# Blue_Pill_-_Display.net
KiCad netlist of a schematic drawn in Altium Designer
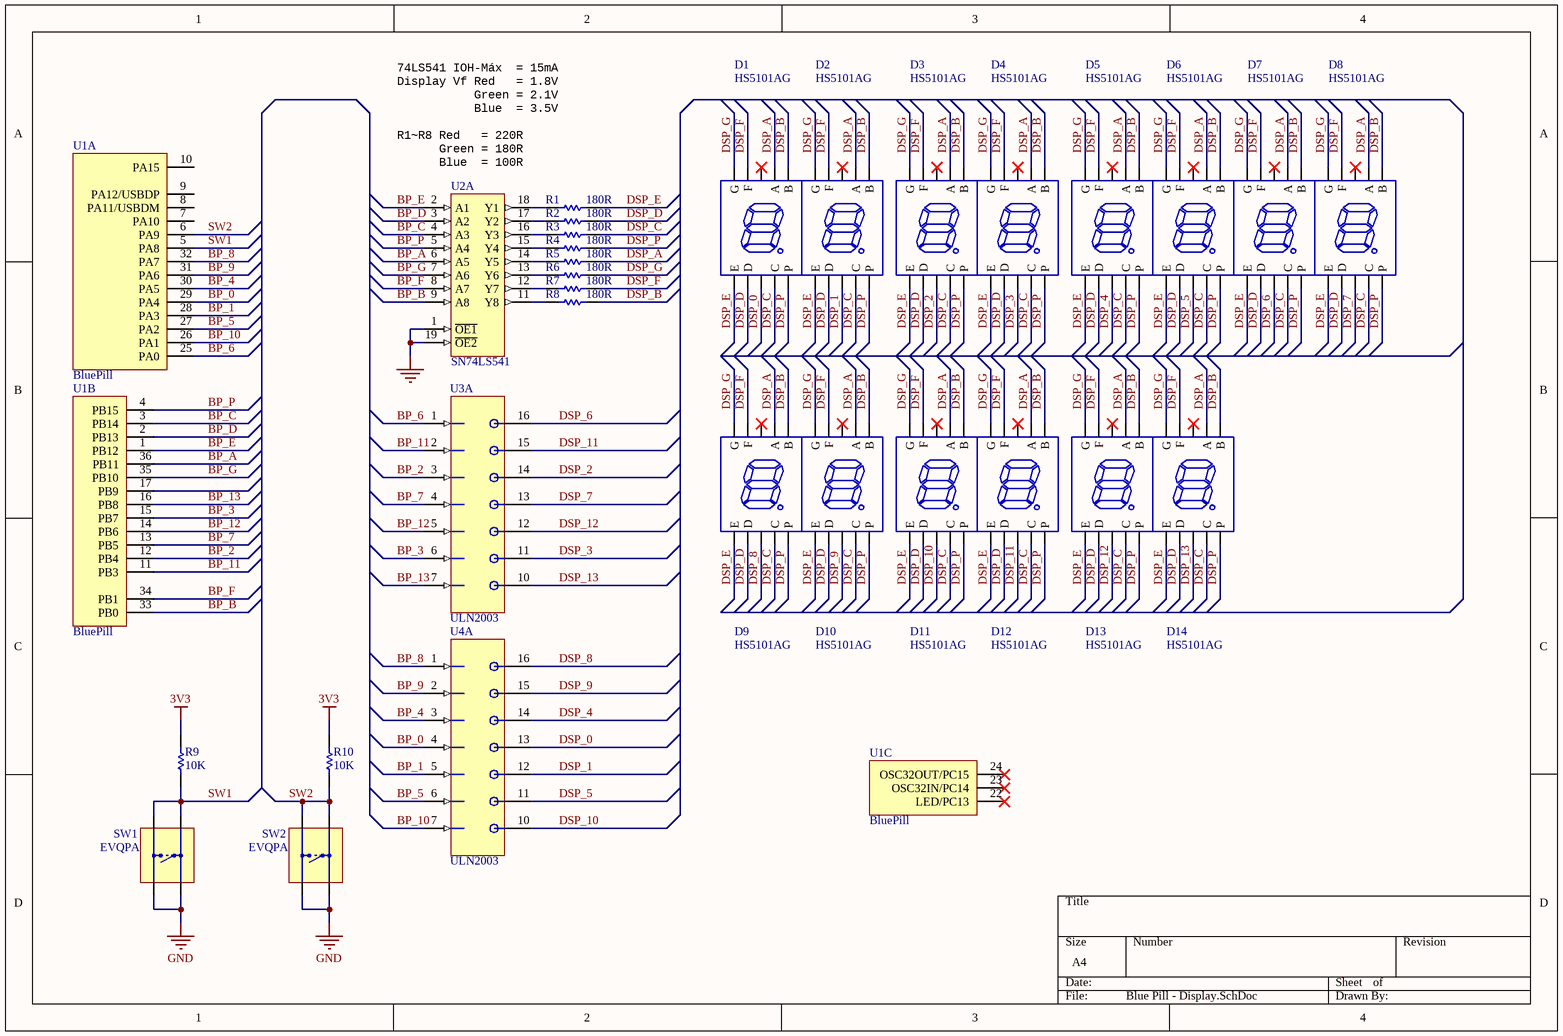
[diagram p0: Blue Pill - Display.SchDoc]

(export (version "E")
  (design (tool "Eeschema 10.0.6"))
  (components
    (comp (ref "D1")
      (value "HS5101AG")
      (footprint "HS5101AG")
      (description "Display 7-Segments Cathodo Common")
      (libsource (lib "Basic") (part "HS5101AG"))
    )
    (comp (ref "D2")
      (value "HS5101AG")
      (footprint "HS5101AG")
      (description "Display 7-Segments Cathodo Common")
      (libsource (lib "Basic") (part "HS5101AG"))
    )
    (comp (ref "D3")
      (value "HS5101AG")
      (footprint "HS5101AG")
      (description "Display 7-Segments Cathodo Common")
      (libsource (lib "Basic") (part "HS5101AG"))
    )
    (comp (ref "D4")
      (value "HS5101AG")
      (footprint "HS5101AG")
      (description "Display 7-Segments Cathodo Common")
      (libsource (lib "Basic") (part "HS5101AG"))
    )
    (comp (ref "D5")
      (value "HS5101AG")
      (footprint "HS5101AG")
      (description "Display 7-Segments Cathodo Common")
      (libsource (lib "Basic") (part "HS5101AG"))
    )
    (comp (ref "D6")
      (value "HS5101AG")
      (footprint "HS5101AG")
      (description "Display 7-Segments Cathodo Common")
      (libsource (lib "Basic") (part "HS5101AG"))
    )
    (comp (ref "D7")
      (value "HS5101AG")
      (footprint "HS5101AG")
      (description "Display 7-Segments Cathodo Common")
      (libsource (lib "Basic") (part "HS5101AG"))
    )
    (comp (ref "D8")
      (value "HS5101AG")
      (footprint "HS5101AG")
      (description "Display 7-Segments Cathodo Common")
      (libsource (lib "Basic") (part "HS5101AG"))
    )
    (comp (ref "D9")
      (value "HS5101AG")
      (footprint "HS5101AG")
      (description "Display 7-Segments Cathodo Common")
      (libsource (lib "Basic") (part "HS5101AG"))
    )
    (comp (ref "D10")
      (value "HS5101AG")
      (footprint "HS5101AG")
      (description "Display 7-Segments Cathodo Common")
      (libsource (lib "Basic") (part "HS5101AG"))
    )
    (comp (ref "D11")
      (value "HS5101AG")
      (footprint "HS5101AG")
      (description "Display 7-Segments Cathodo Common")
      (libsource (lib "Basic") (part "HS5101AG"))
    )
    (comp (ref "D12")
      (value "HS5101AG")
      (footprint "HS5101AG")
      (description "Display 7-Segments Cathodo Common")
      (libsource (lib "Basic") (part "HS5101AG"))
    )
    (comp (ref "D13")
      (value "HS5101AG")
      (footprint "HS5101AG")
      (description "Display 7-Segments Cathodo Common")
      (libsource (lib "Basic") (part "HS5101AG"))
    )
    (comp (ref "D14")
      (value "HS5101AG")
      (footprint "HS5101AG")
      (description "Display 7-Segments Cathodo Common")
      (libsource (lib "Basic") (part "HS5101AG"))
    )
    (comp (ref "R1")
      (value "180R")
      (footprint "0805")
      (description "Resistor")
      (libsource (lib "Basic") (part "Resistor"))
    )
    (comp (ref "R2")
      (value "180R")
      (footprint "0805")
      (description "Resistor")
      (libsource (lib "Basic") (part "Resistor"))
    )
    (comp (ref "R3")
      (value "180R")
      (footprint "0805")
      (description "Resistor")
      (libsource (lib "Basic") (part "Resistor"))
    )
    (comp (ref "R4")
      (value "180R")
      (footprint "0805")
      (description "Resistor")
      (libsource (lib "Basic") (part "Resistor"))
    )
    (comp (ref "R5")
      (value "180R")
      (footprint "0805")
      (description "Resistor")
      (libsource (lib "Basic") (part "Resistor"))
    )
    (comp (ref "R6")
      (value "180R")
      (footprint "0805")
      (description "Resistor")
      (libsource (lib "Basic") (part "Resistor"))
    )
    (comp (ref "R7")
      (value "180R")
      (footprint "0805")
      (description "Resistor")
      (libsource (lib "Basic") (part "Resistor"))
    )
    (comp (ref "R8")
      (value "180R")
      (footprint "0805")
      (description "Resistor")
      (libsource (lib "Basic") (part "Resistor"))
    )
    (comp (ref "R9")
      (value "10K")
      (footprint "0805")
      (description "Resistor")
      (libsource (lib "Basic") (part "Resistor"))
    )
    (comp (ref "R10")
      (value "10K")
      (footprint "0805")
      (description "Resistor")
      (libsource (lib "Basic") (part "Resistor"))
    )
    (comp (ref "SW1")
      (value "EVQPA")
      (footprint "EVQPAx09K")
      (description "5N Type Light Touch Switches")
      (libsource (lib "Panasonic") (part "EVQPA"))
    )
    (comp (ref "SW2")
      (value "EVQPA")
      (footprint "EVQPAx09K")
      (description "5N Type Light Touch Switches")
      (libsource (lib "Panasonic") (part "EVQPA"))
    )
    (comp (ref "U1")
      (value "BluePill")
      (footprint "Blue Pill")
      (description "STM32 Blue Pill")
      (libsource (lib "STM32 Blue Pill") (part "Blue Pill - Model 1"))
    )
    (comp (ref "U2")
      (value "SN74LS541")
      (footprint "PDIP20")
      (description "Octal Buffers and Line Drivers With 3-State Outputs")
      (libsource (lib "Texas Instruments") (part "SN74HC541 Type-2"))
    )
    (comp (ref "U3")
      (value "ULN2003")
      (footprint "PDIP16")
      (description "Seven Darlington arrays")
      (libsource (lib "ST Microelectronics") (part "UN200x - Model 1"))
    )
    (comp (ref "U4")
      (value "ULN2003")
      (footprint "PDIP16")
      (description "Seven Darlington arrays")
      (libsource (lib "ST Microelectronics") (part "UN200x - Model 1"))
    )
  )
  (nets
    (net (code "1") (name "/BP_0") (class "Default")
      (node (ref "U1") (pin "29") (pinfunction "PA4_29") (pintype "passive"))
      (node (ref "U4") (pin "4") (pinfunction "4_4") (pintype "input"))
    )
    (net (code "2") (name "/BP_1") (class "Default")
      (node (ref "U1") (pin "28") (pinfunction "PA3_28") (pintype "passive"))
      (node (ref "U4") (pin "5") (pinfunction "5_5") (pintype "input"))
    )
    (net (code "3") (name "/BP_2") (class "Default")
      (node (ref "U1") (pin "12") (pinfunction "PB4_12") (pintype "passive"))
      (node (ref "U3") (pin "3") (pinfunction "3_3") (pintype "input"))
    )
    (net (code "4") (name "/BP_3") (class "Default")
      (node (ref "U1") (pin "15") (pinfunction "PB7_15") (pintype "passive"))
      (node (ref "U3") (pin "6") (pinfunction "6_6") (pintype "input"))
    )
    (net (code "5") (name "/BP_4") (class "Default")
      (node (ref "U1") (pin "30") (pinfunction "PA5_30") (pintype "passive"))
      (node (ref "U4") (pin "3") (pinfunction "3_3") (pintype "input"))
    )
    (net (code "6") (name "/BP_5") (class "Default")
      (node (ref "U1") (pin "27") (pinfunction "PA2_27") (pintype "passive"))
      (node (ref "U4") (pin "6") (pinfunction "6_6") (pintype "input"))
    )
    (net (code "7") (name "/BP_6") (class "Default")
      (node (ref "U1") (pin "25") (pinfunction "PA0_25") (pintype "passive"))
      (node (ref "U3") (pin "1") (pinfunction "1_1") (pintype "input"))
    )
    (net (code "8") (name "/BP_7") (class "Default")
      (node (ref "U1") (pin "13") (pinfunction "PB5_13") (pintype "passive"))
      (node (ref "U3") (pin "4") (pinfunction "4_4") (pintype "input"))
    )
    (net (code "9") (name "/BP_8") (class "Default")
      (node (ref "U1") (pin "32") (pinfunction "PA7_32") (pintype "passive"))
      (node (ref "U4") (pin "1") (pinfunction "1_1") (pintype "input"))
    )
    (net (code "10") (name "/BP_9") (class "Default")
      (node (ref "U1") (pin "31") (pinfunction "PA6_31") (pintype "passive"))
      (node (ref "U4") (pin "2") (pinfunction "2_2") (pintype "input"))
    )
    (net (code "11") (name "/BP_10") (class "Default")
      (node (ref "U1") (pin "26") (pinfunction "PA1_26") (pintype "passive"))
      (node (ref "U4") (pin "7") (pinfunction "7_7") (pintype "input"))
    )
    (net (code "12") (name "/BP_11") (class "Default")
      (node (ref "U1") (pin "11") (pinfunction "PB3_11") (pintype "passive"))
      (node (ref "U3") (pin "2") (pinfunction "2_2") (pintype "input"))
    )
    (net (code "13") (name "/BP_12") (class "Default")
      (node (ref "U1") (pin "14") (pinfunction "PB6_14") (pintype "passive"))
      (node (ref "U3") (pin "5") (pinfunction "5_5") (pintype "input"))
    )
    (net (code "14") (name "/BP_13") (class "Default")
      (node (ref "U1") (pin "16") (pinfunction "PB8_16") (pintype "passive"))
      (node (ref "U3") (pin "7") (pinfunction "7_7") (pintype "input"))
    )
    (net (code "15") (name "/BP_A") (class "Default")
      (node (ref "U1") (pin "36") (pinfunction "PB11_36") (pintype "passive"))
      (node (ref "U2") (pin "6") (pinfunction "A5_6") (pintype "input"))
    )
    (net (code "16") (name "/BP_B") (class "Default")
      (node (ref "U1") (pin "33") (pinfunction "PB0_33") (pintype "passive"))
      (node (ref "U2") (pin "9") (pinfunction "A8_9") (pintype "input"))
    )
    (net (code "17") (name "/BP_C") (class "Default")
      (node (ref "U1") (pin "3") (pinfunction "PB14_3") (pintype "passive"))
      (node (ref "U2") (pin "4") (pinfunction "A3_4") (pintype "input"))
    )
    (net (code "18") (name "/BP_D") (class "Default")
      (node (ref "U1") (pin "2") (pinfunction "PB13_2") (pintype "passive"))
      (node (ref "U2") (pin "3") (pinfunction "A2_3") (pintype "input"))
    )
    (net (code "19") (name "/BP_E") (class "Default")
      (node (ref "U1") (pin "1") (pinfunction "PB12_1") (pintype "passive"))
      (node (ref "U2") (pin "2") (pinfunction "A1_2") (pintype "input"))
    )
    (net (code "20") (name "/BP_F") (class "Default")
      (node (ref "U1") (pin "34") (pinfunction "PB1_34") (pintype "passive"))
      (node (ref "U2") (pin "8") (pinfunction "A7_8") (pintype "input"))
    )
    (net (code "21") (name "/BP_G") (class "Default")
      (node (ref "U1") (pin "35") (pinfunction "PB10_35") (pintype "passive"))
      (node (ref "U2") (pin "7") (pinfunction "A6_7") (pintype "input"))
    )
    (net (code "22") (name "/BP_P") (class "Default")
      (node (ref "U1") (pin "4") (pinfunction "PB15_4") (pintype "passive"))
      (node (ref "U2") (pin "5") (pinfunction "A4_5") (pintype "input"))
    )
    (net (code "23") (name "/DSP_0") (class "Default")
      (node (ref "D1") (pin "3") (pinfunction "GND2_3") (pintype "power_in"))
      (node (ref "U4") (pin "13") (pinfunction "13_13") (pintype "open_collector"))
    )
    (net (code "24") (name "/DSP_1") (class "Default")
      (node (ref "D2") (pin "3") (pinfunction "GND2_3") (pintype "power_in"))
      (node (ref "U4") (pin "12") (pinfunction "12_12") (pintype "open_collector"))
    )
    (net (code "25") (name "/DSP_2") (class "Default")
      (node (ref "D3") (pin "3") (pinfunction "GND2_3") (pintype "power_in"))
      (node (ref "U3") (pin "14") (pinfunction "14_14") (pintype "open_collector"))
    )
    (net (code "26") (name "/DSP_3") (class "Default")
      (node (ref "D4") (pin "3") (pinfunction "GND2_3") (pintype "power_in"))
      (node (ref "U3") (pin "11") (pinfunction "11_11") (pintype "open_collector"))
    )
    (net (code "27") (name "/DSP_4") (class "Default")
      (node (ref "D5") (pin "3") (pinfunction "GND2_3") (pintype "power_in"))
      (node (ref "U4") (pin "14") (pinfunction "14_14") (pintype "open_collector"))
    )
    (net (code "28") (name "/DSP_5") (class "Default")
      (node (ref "D6") (pin "3") (pinfunction "GND2_3") (pintype "power_in"))
      (node (ref "U4") (pin "11") (pinfunction "11_11") (pintype "open_collector"))
    )
    (net (code "29") (name "/DSP_6") (class "Default")
      (node (ref "D7") (pin "3") (pinfunction "GND2_3") (pintype "power_in"))
      (node (ref "U3") (pin "16") (pinfunction "16_16") (pintype "open_collector"))
    )
    (net (code "30") (name "/DSP_7") (class "Default")
      (node (ref "D8") (pin "3") (pinfunction "GND2_3") (pintype "power_in"))
      (node (ref "U3") (pin "13") (pinfunction "13_13") (pintype "open_collector"))
    )
    (net (code "31") (name "/DSP_8") (class "Default")
      (node (ref "D9") (pin "3") (pinfunction "GND2_3") (pintype "power_in"))
      (node (ref "U4") (pin "16") (pinfunction "16_16") (pintype "open_collector"))
    )
    (net (code "32") (name "/DSP_9") (class "Default")
      (node (ref "D10") (pin "3") (pinfunction "GND2_3") (pintype "power_in"))
      (node (ref "U4") (pin "15") (pinfunction "15_15") (pintype "open_collector"))
    )
    (net (code "33") (name "/DSP_10") (class "Default")
      (node (ref "D11") (pin "3") (pinfunction "GND2_3") (pintype "power_in"))
      (node (ref "U4") (pin "10") (pinfunction "10_10") (pintype "open_collector"))
    )
    (net (code "34") (name "/DSP_11") (class "Default")
      (node (ref "D12") (pin "3") (pinfunction "GND2_3") (pintype "power_in"))
      (node (ref "U3") (pin "15") (pinfunction "15_15") (pintype "open_collector"))
    )
    (net (code "35") (name "/DSP_12") (class "Default")
      (node (ref "D13") (pin "3") (pinfunction "GND2_3") (pintype "power_in"))
      (node (ref "U3") (pin "12") (pinfunction "12_12") (pintype "open_collector"))
    )
    (net (code "36") (name "/DSP_13") (class "Default")
      (node (ref "D14") (pin "3") (pinfunction "GND2_3") (pintype "power_in"))
      (node (ref "U3") (pin "10") (pinfunction "10_10") (pintype "open_collector"))
    )
    (net (code "37") (name "/DSP_A") (class "Default")
      (node (ref "D1") (pin "7") (pinfunction "A_7") (pintype "passive"))
      (node (ref "D10") (pin "7") (pinfunction "A_7") (pintype "passive"))
      (node (ref "D11") (pin "7") (pinfunction "A_7") (pintype "passive"))
      (node (ref "D12") (pin "7") (pinfunction "A_7") (pintype "passive"))
      (node (ref "D13") (pin "7") (pinfunction "A_7") (pintype "passive"))
      (node (ref "D14") (pin "7") (pinfunction "A_7") (pintype "passive"))
      (node (ref "D2") (pin "7") (pinfunction "A_7") (pintype "passive"))
      (node (ref "D3") (pin "7") (pinfunction "A_7") (pintype "passive"))
      (node (ref "D4") (pin "7") (pinfunction "A_7") (pintype "passive"))
      (node (ref "D5") (pin "7") (pinfunction "A_7") (pintype "passive"))
      (node (ref "D6") (pin "7") (pinfunction "A_7") (pintype "passive"))
      (node (ref "D7") (pin "7") (pinfunction "A_7") (pintype "passive"))
      (node (ref "D8") (pin "7") (pinfunction "A_7") (pintype "passive"))
      (node (ref "D9") (pin "7") (pinfunction "A_7") (pintype "passive"))
      (node (ref "R5") (pin "2") (pinfunction "2_2") (pintype "passive"))
    )
    (net (code "38") (name "/DSP_B") (class "Default")
      (node (ref "D1") (pin "6") (pinfunction "B_6") (pintype "passive"))
      (node (ref "D10") (pin "6") (pinfunction "B_6") (pintype "passive"))
      (node (ref "D11") (pin "6") (pinfunction "B_6") (pintype "passive"))
      (node (ref "D12") (pin "6") (pinfunction "B_6") (pintype "passive"))
      (node (ref "D13") (pin "6") (pinfunction "B_6") (pintype "passive"))
      (node (ref "D14") (pin "6") (pinfunction "B_6") (pintype "passive"))
      (node (ref "D2") (pin "6") (pinfunction "B_6") (pintype "passive"))
      (node (ref "D3") (pin "6") (pinfunction "B_6") (pintype "passive"))
      (node (ref "D4") (pin "6") (pinfunction "B_6") (pintype "passive"))
      (node (ref "D5") (pin "6") (pinfunction "B_6") (pintype "passive"))
      (node (ref "D6") (pin "6") (pinfunction "B_6") (pintype "passive"))
      (node (ref "D7") (pin "6") (pinfunction "B_6") (pintype "passive"))
      (node (ref "D8") (pin "6") (pinfunction "B_6") (pintype "passive"))
      (node (ref "D9") (pin "6") (pinfunction "B_6") (pintype "passive"))
      (node (ref "R8") (pin "2") (pinfunction "2_2") (pintype "passive"))
    )
    (net (code "39") (name "/DSP_C") (class "Default")
      (node (ref "D1") (pin "4") (pinfunction "C_4") (pintype "passive"))
      (node (ref "D10") (pin "4") (pinfunction "C_4") (pintype "passive"))
      (node (ref "D11") (pin "4") (pinfunction "C_4") (pintype "passive"))
      (node (ref "D12") (pin "4") (pinfunction "C_4") (pintype "passive"))
      (node (ref "D13") (pin "4") (pinfunction "C_4") (pintype "passive"))
      (node (ref "D14") (pin "4") (pinfunction "C_4") (pintype "passive"))
      (node (ref "D2") (pin "4") (pinfunction "C_4") (pintype "passive"))
      (node (ref "D3") (pin "4") (pinfunction "C_4") (pintype "passive"))
      (node (ref "D4") (pin "4") (pinfunction "C_4") (pintype "passive"))
      (node (ref "D5") (pin "4") (pinfunction "C_4") (pintype "passive"))
      (node (ref "D6") (pin "4") (pinfunction "C_4") (pintype "passive"))
      (node (ref "D7") (pin "4") (pinfunction "C_4") (pintype "passive"))
      (node (ref "D8") (pin "4") (pinfunction "C_4") (pintype "passive"))
      (node (ref "D9") (pin "4") (pinfunction "C_4") (pintype "passive"))
      (node (ref "R3") (pin "2") (pinfunction "2_2") (pintype "passive"))
    )
    (net (code "40") (name "/DSP_D") (class "Default")
      (node (ref "D1") (pin "2") (pinfunction "D_2") (pintype "passive"))
      (node (ref "D10") (pin "2") (pinfunction "D_2") (pintype "passive"))
      (node (ref "D11") (pin "2") (pinfunction "D_2") (pintype "passive"))
      (node (ref "D12") (pin "2") (pinfunction "D_2") (pintype "passive"))
      (node (ref "D13") (pin "2") (pinfunction "D_2") (pintype "passive"))
      (node (ref "D14") (pin "2") (pinfunction "D_2") (pintype "passive"))
      (node (ref "D2") (pin "2") (pinfunction "D_2") (pintype "passive"))
      (node (ref "D3") (pin "2") (pinfunction "D_2") (pintype "passive"))
      (node (ref "D4") (pin "2") (pinfunction "D_2") (pintype "passive"))
      (node (ref "D5") (pin "2") (pinfunction "D_2") (pintype "passive"))
      (node (ref "D6") (pin "2") (pinfunction "D_2") (pintype "passive"))
      (node (ref "D7") (pin "2") (pinfunction "D_2") (pintype "passive"))
      (node (ref "D8") (pin "2") (pinfunction "D_2") (pintype "passive"))
      (node (ref "D9") (pin "2") (pinfunction "D_2") (pintype "passive"))
      (node (ref "R2") (pin "2") (pinfunction "2_2") (pintype "passive"))
    )
    (net (code "41") (name "/DSP_E") (class "Default")
      (node (ref "D1") (pin "1") (pinfunction "E_1") (pintype "passive"))
      (node (ref "D10") (pin "1") (pinfunction "E_1") (pintype "passive"))
      (node (ref "D11") (pin "1") (pinfunction "E_1") (pintype "passive"))
      (node (ref "D12") (pin "1") (pinfunction "E_1") (pintype "passive"))
      (node (ref "D13") (pin "1") (pinfunction "E_1") (pintype "passive"))
      (node (ref "D14") (pin "1") (pinfunction "E_1") (pintype "passive"))
      (node (ref "D2") (pin "1") (pinfunction "E_1") (pintype "passive"))
      (node (ref "D3") (pin "1") (pinfunction "E_1") (pintype "passive"))
      (node (ref "D4") (pin "1") (pinfunction "E_1") (pintype "passive"))
      (node (ref "D5") (pin "1") (pinfunction "E_1") (pintype "passive"))
      (node (ref "D6") (pin "1") (pinfunction "E_1") (pintype "passive"))
      (node (ref "D7") (pin "1") (pinfunction "E_1") (pintype "passive"))
      (node (ref "D8") (pin "1") (pinfunction "E_1") (pintype "passive"))
      (node (ref "D9") (pin "1") (pinfunction "E_1") (pintype "passive"))
      (node (ref "R1") (pin "2") (pinfunction "2_2") (pintype "passive"))
    )
    (net (code "42") (name "/DSP_F") (class "Default")
      (node (ref "D1") (pin "9") (pinfunction "F_9") (pintype "passive"))
      (node (ref "D10") (pin "9") (pinfunction "F_9") (pintype "passive"))
      (node (ref "D11") (pin "9") (pinfunction "F_9") (pintype "passive"))
      (node (ref "D12") (pin "9") (pinfunction "F_9") (pintype "passive"))
      (node (ref "D13") (pin "9") (pinfunction "F_9") (pintype "passive"))
      (node (ref "D14") (pin "9") (pinfunction "F_9") (pintype "passive"))
      (node (ref "D2") (pin "9") (pinfunction "F_9") (pintype "passive"))
      (node (ref "D3") (pin "9") (pinfunction "F_9") (pintype "passive"))
      (node (ref "D4") (pin "9") (pinfunction "F_9") (pintype "passive"))
      (node (ref "D5") (pin "9") (pinfunction "F_9") (pintype "passive"))
      (node (ref "D6") (pin "9") (pinfunction "F_9") (pintype "passive"))
      (node (ref "D7") (pin "9") (pinfunction "F_9") (pintype "passive"))
      (node (ref "D8") (pin "9") (pinfunction "F_9") (pintype "passive"))
      (node (ref "D9") (pin "9") (pinfunction "F_9") (pintype "passive"))
      (node (ref "R7") (pin "2") (pinfunction "2_2") (pintype "passive"))
    )
    (net (code "43") (name "/DSP_G") (class "Default")
      (node (ref "D1") (pin "10") (pinfunction "G_10") (pintype "passive"))
      (node (ref "D10") (pin "10") (pinfunction "G_10") (pintype "passive"))
      (node (ref "D11") (pin "10") (pinfunction "G_10") (pintype "passive"))
      (node (ref "D12") (pin "10") (pinfunction "G_10") (pintype "passive"))
      (node (ref "D13") (pin "10") (pinfunction "G_10") (pintype "passive"))
      (node (ref "D14") (pin "10") (pinfunction "G_10") (pintype "passive"))
      (node (ref "D2") (pin "10") (pinfunction "G_10") (pintype "passive"))
      (node (ref "D3") (pin "10") (pinfunction "G_10") (pintype "passive"))
      (node (ref "D4") (pin "10") (pinfunction "G_10") (pintype "passive"))
      (node (ref "D5") (pin "10") (pinfunction "G_10") (pintype "passive"))
      (node (ref "D6") (pin "10") (pinfunction "G_10") (pintype "passive"))
      (node (ref "D7") (pin "10") (pinfunction "G_10") (pintype "passive"))
      (node (ref "D8") (pin "10") (pinfunction "G_10") (pintype "passive"))
      (node (ref "D9") (pin "10") (pinfunction "G_10") (pintype "passive"))
      (node (ref "R6") (pin "2") (pinfunction "2_2") (pintype "passive"))
    )
    (net (code "44") (name "/DSP_P") (class "Default")
      (node (ref "D1") (pin "5") (pinfunction "P_5") (pintype "passive"))
      (node (ref "D10") (pin "5") (pinfunction "P_5") (pintype "passive"))
      (node (ref "D11") (pin "5") (pinfunction "P_5") (pintype "passive"))
      (node (ref "D12") (pin "5") (pinfunction "P_5") (pintype "passive"))
      (node (ref "D13") (pin "5") (pinfunction "P_5") (pintype "passive"))
      (node (ref "D14") (pin "5") (pinfunction "P_5") (pintype "passive"))
      (node (ref "D2") (pin "5") (pinfunction "P_5") (pintype "passive"))
      (node (ref "D3") (pin "5") (pinfunction "P_5") (pintype "passive"))
      (node (ref "D4") (pin "5") (pinfunction "P_5") (pintype "passive"))
      (node (ref "D5") (pin "5") (pinfunction "P_5") (pintype "passive"))
      (node (ref "D6") (pin "5") (pinfunction "P_5") (pintype "passive"))
      (node (ref "D7") (pin "5") (pinfunction "P_5") (pintype "passive"))
      (node (ref "D8") (pin "5") (pinfunction "P_5") (pintype "passive"))
      (node (ref "D9") (pin "5") (pinfunction "P_5") (pintype "passive"))
      (node (ref "R4") (pin "2") (pinfunction "2_2") (pintype "passive"))
    )
    (net (code "45") (name "/SW1") (class "Default")
      (node (ref "R9") (pin "1") (pinfunction "1_1") (pintype "passive"))
      (node (ref "SW1") (pin "3") (pinfunction "3_3") (pintype "power_in"))
      (node (ref "SW1") (pin "4") (pinfunction "4_4") (pintype "power_in"))
      (node (ref "U1") (pin "5") (pinfunction "PA8_5") (pintype "passive"))
    )
    (net (code "46") (name "/SW2") (class "Default")
      (node (ref "R10") (pin "1") (pinfunction "1_1") (pintype "passive"))
      (node (ref "SW2") (pin "3") (pinfunction "3_3") (pintype "power_in"))
      (node (ref "SW2") (pin "4") (pinfunction "4_4") (pintype "power_in"))
      (node (ref "U1") (pin "6") (pinfunction "PA9_6") (pintype "passive"))
    )
    (net (code "47") (name "3V3") (class "Default")
      (node (ref "R10") (pin "2") (pinfunction "2_2") (pintype "passive"))
      (node (ref "R9") (pin "2") (pinfunction "2_2") (pintype "passive"))
    )
    (net (code "48") (name "GND") (class "Default")
      (node (ref "SW1") (pin "1") (pinfunction "1_1") (pintype "power_in"))
      (node (ref "SW1") (pin "2") (pinfunction "2_2") (pintype "power_in"))
      (node (ref "SW2") (pin "1") (pinfunction "1_1") (pintype "power_in"))
      (node (ref "SW2") (pin "2") (pinfunction "2_2") (pintype "power_in"))
      (node (ref "U2") (pin "1") (pinfunction "~{OE1}_1") (pintype "input"))
      (node (ref "U2") (pin "19") (pinfunction "~{OE2}_19") (pintype "input"))
    )
    (net (code "49") (name "Net-(U2A-Y1)") (class "Default")
      (node (ref "R1") (pin "1") (pinfunction "1_1") (pintype "passive"))
      (node (ref "U2") (pin "18") (pinfunction "Y1_18") (pintype "output"))
    )
    (net (code "50") (name "Net-(U2A-Y2)") (class "Default")
      (node (ref "R2") (pin "1") (pinfunction "1_1") (pintype "passive"))
      (node (ref "U2") (pin "17") (pinfunction "Y2_17") (pintype "output"))
    )
    (net (code "51") (name "Net-(U2A-Y3)") (class "Default")
      (node (ref "R3") (pin "1") (pinfunction "1_1") (pintype "passive"))
      (node (ref "U2") (pin "16") (pinfunction "Y3_16") (pintype "output"))
    )
    (net (code "52") (name "Net-(U2A-Y4)") (class "Default")
      (node (ref "R4") (pin "1") (pinfunction "1_1") (pintype "passive"))
      (node (ref "U2") (pin "15") (pinfunction "Y4_15") (pintype "output"))
    )
    (net (code "53") (name "Net-(U2A-Y5)") (class "Default")
      (node (ref "R5") (pin "1") (pinfunction "1_1") (pintype "passive"))
      (node (ref "U2") (pin "14") (pinfunction "Y5_14") (pintype "output"))
    )
    (net (code "54") (name "Net-(U2A-Y6)") (class "Default")
      (node (ref "R6") (pin "1") (pinfunction "1_1") (pintype "passive"))
      (node (ref "U2") (pin "13") (pinfunction "Y6_13") (pintype "output"))
    )
    (net (code "55") (name "Net-(U2A-Y7)") (class "Default")
      (node (ref "R7") (pin "1") (pinfunction "1_1") (pintype "passive"))
      (node (ref "U2") (pin "12") (pinfunction "Y7_12") (pintype "output"))
    )
    (net (code "56") (name "Net-(U2A-Y8)") (class "Default")
      (node (ref "R8") (pin "1") (pinfunction "1_1") (pintype "passive"))
      (node (ref "U2") (pin "11") (pinfunction "Y8_11") (pintype "output"))
    )
    (net (code "57") (name "unconnected-(D1-GND1-Pad8)") (class "Default")
      (node (ref "D1") (pin "8") (pinfunction "GND1_8") (pintype "power_in+no_connect"))
    )
    (net (code "58") (name "unconnected-(D2-GND1-Pad8)") (class "Default")
      (node (ref "D2") (pin "8") (pinfunction "GND1_8") (pintype "power_in+no_connect"))
    )
    (net (code "59") (name "unconnected-(D3-GND1-Pad8)") (class "Default")
      (node (ref "D3") (pin "8") (pinfunction "GND1_8") (pintype "power_in+no_connect"))
    )
    (net (code "60") (name "unconnected-(D4-GND1-Pad8)") (class "Default")
      (node (ref "D4") (pin "8") (pinfunction "GND1_8") (pintype "power_in+no_connect"))
    )
    (net (code "61") (name "unconnected-(D5-GND1-Pad8)") (class "Default")
      (node (ref "D5") (pin "8") (pinfunction "GND1_8") (pintype "power_in+no_connect"))
    )
    (net (code "62") (name "unconnected-(D6-GND1-Pad8)") (class "Default")
      (node (ref "D6") (pin "8") (pinfunction "GND1_8") (pintype "power_in+no_connect"))
    )
    (net (code "63") (name "unconnected-(D7-GND1-Pad8)") (class "Default")
      (node (ref "D7") (pin "8") (pinfunction "GND1_8") (pintype "power_in+no_connect"))
    )
    (net (code "64") (name "unconnected-(D8-GND1-Pad8)") (class "Default")
      (node (ref "D8") (pin "8") (pinfunction "GND1_8") (pintype "power_in+no_connect"))
    )
    (net (code "65") (name "unconnected-(D9-GND1-Pad8)") (class "Default")
      (node (ref "D9") (pin "8") (pinfunction "GND1_8") (pintype "power_in+no_connect"))
    )
    (net (code "66") (name "unconnected-(D10-GND1-Pad8)") (class "Default")
      (node (ref "D10") (pin "8") (pinfunction "GND1_8") (pintype "power_in+no_connect"))
    )
    (net (code "67") (name "unconnected-(D11-GND1-Pad8)") (class "Default")
      (node (ref "D11") (pin "8") (pinfunction "GND1_8") (pintype "power_in+no_connect"))
    )
    (net (code "68") (name "unconnected-(D12-GND1-Pad8)") (class "Default")
      (node (ref "D12") (pin "8") (pinfunction "GND1_8") (pintype "power_in+no_connect"))
    )
    (net (code "69") (name "unconnected-(D13-GND1-Pad8)") (class "Default")
      (node (ref "D13") (pin "8") (pinfunction "GND1_8") (pintype "power_in+no_connect"))
    )
    (net (code "70") (name "unconnected-(D14-GND1-Pad8)") (class "Default")
      (node (ref "D14") (pin "8") (pinfunction "GND1_8") (pintype "power_in+no_connect"))
    )
    (net (code "71") (name "unconnected-(U1A-PA10-Pad7)") (class "Default")
      (node (ref "U1") (pin "7") (pinfunction "PA10_7") (pintype "passive"))
    )
    (net (code "72") (name "unconnected-(U1A-PA11{slash}USBDM-Pad8)") (class "Default")
      (node (ref "U1") (pin "8") (pinfunction "PA11/USBDM_8") (pintype "passive"))
    )
    (net (code "73") (name "unconnected-(U1A-PA12{slash}USBDP-Pad9)") (class "Default")
      (node (ref "U1") (pin "9") (pinfunction "PA12/USBDP_9") (pintype "passive"))
    )
    (net (code "74") (name "unconnected-(U1A-PA15-Pad10)") (class "Default")
      (node (ref "U1") (pin "10") (pinfunction "PA15_10") (pintype "passive"))
    )
    (net (code "75") (name "unconnected-(U1B-PB9-Pad17)") (class "Default")
      (node (ref "U1") (pin "17") (pinfunction "PB9_17") (pintype "passive"))
    )
    (net (code "76") (name "unconnected-(U1C-LED{slash}PC13-Pad22)") (class "Default")
      (node (ref "U1") (pin "22") (pinfunction "LED/PC13_22") (pintype "passive+no_connect"))
    )
    (net (code "77") (name "unconnected-(U1C-OSC32IN{slash}PC14-Pad23)") (class "Default")
      (node (ref "U1") (pin "23") (pinfunction "OSC32IN/PC14_23") (pintype "passive+no_connect"))
    )
    (net (code "78") (name "unconnected-(U1C-OSC32OUT{slash}PC15-Pad24)") (class "Default")
      (node (ref "U1") (pin "24") (pinfunction "OSC32OUT/PC15_24") (pintype "passive+no_connect"))
    )
  )
)
